# moon-germs.net
KiCad netlist of a schematic drawn in EAGLE
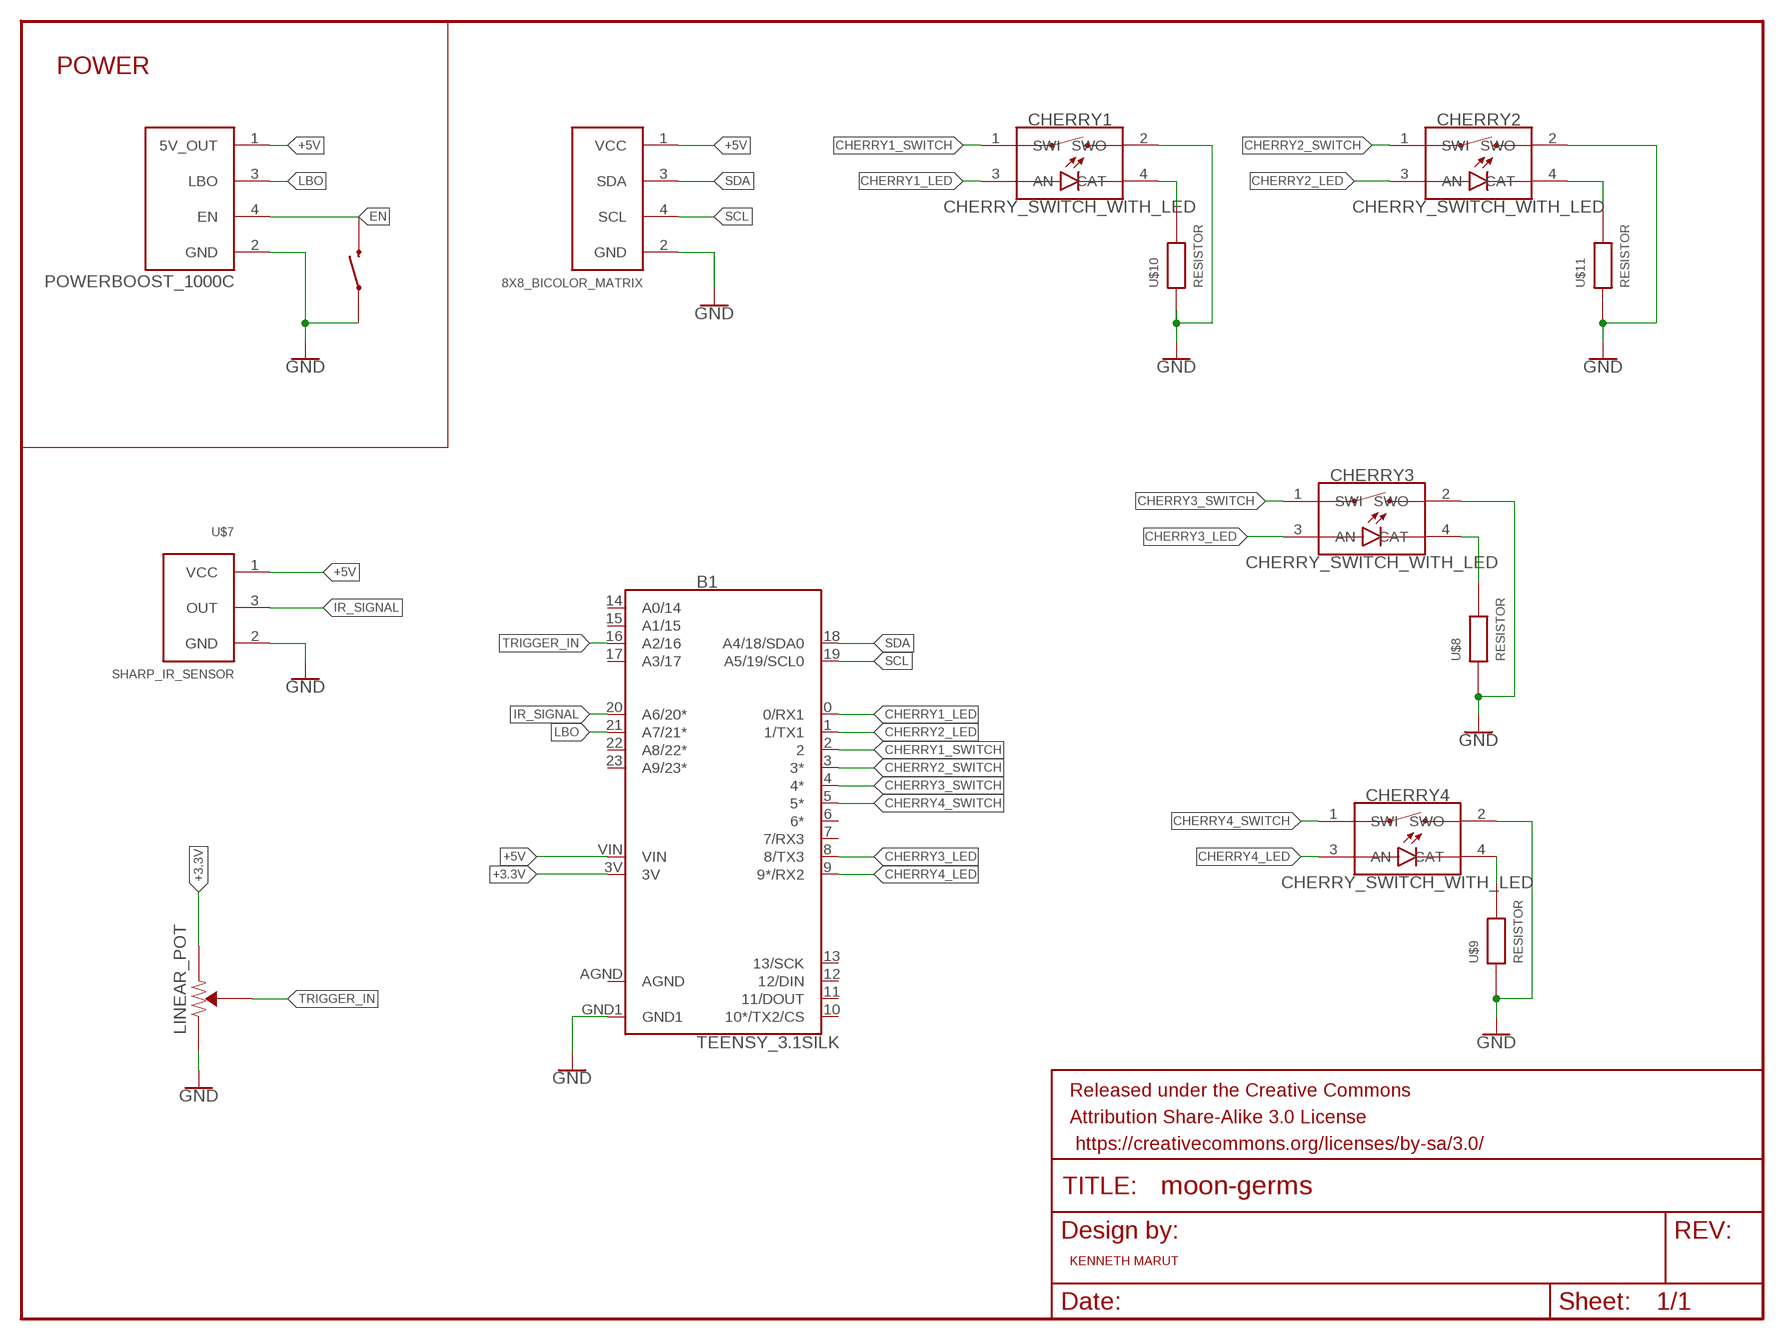
[diagram p0: schematic, sheet 1]

(export (version "E")
  (design (tool "Eeschema 10.0.6"))
  (components
    (comp (ref "B1")
      (value "TEENSY_3.1SILK")
      (footprint "eagle-import:TEENSY_3.1")
      (libsource (lib "eagle-import") (part "TEENSY_3.1SILK"))
    )
    (comp (ref "CHERRY1")
      (value "CHERRY_SWITCH_WITH_LED")
      (footprint "eagle-import:1X04")
      (libsource (lib "eagle-import") (part "CHERRY_SWITCH_WITH_LED"))
    )
    (comp (ref "CHERRY2")
      (value "CHERRY_SWITCH_WITH_LED")
      (footprint "eagle-import:1X04")
      (libsource (lib "eagle-import") (part "CHERRY_SWITCH_WITH_LED"))
    )
    (comp (ref "CHERRY3")
      (value "CHERRY_SWITCH_WITH_LED")
      (footprint "eagle-import:1X04")
      (libsource (lib "eagle-import") (part "CHERRY_SWITCH_WITH_LED"))
    )
    (comp (ref "CHERRY4")
      (value "CHERRY_SWITCH_WITH_LED")
      (footprint "eagle-import:1X04")
      (libsource (lib "eagle-import") (part "CHERRY_SWITCH_WITH_LED"))
    )
    (comp (ref "FRAME1")
      (value "FRAME-LETTER")
      (footprint "eagle-import:CREATIVE_COMMONS")
      (libsource (lib "eagle-import") (part "FRAME-LETTER"))
    )
    (comp (ref "U$1")
      (value "8X8_BICOLOR_MATRIX")
      (footprint "eagle-import:1X04")
      (libsource (lib "eagle-import") (part "8X8_BICOLOR_MATRIX"))
    )
    (comp (ref "U$6")
      (value "SPST-SWITCH")
      (footprint "eagle-import:1X02")
      (libsource (lib "eagle-import") (part "SPST-SWITCH"))
    )
    (comp (ref "U$7")
      (value "SHARP_IR_SENSOR")
      (footprint "eagle-import:1X03")
      (libsource (lib "eagle-import") (part "SHARP_IR_SENSOR"))
    )
    (comp (ref "U$8")
      (value "RESISTOR")
      (footprint "eagle-import:0805")
      (libsource (lib "eagle-import") (part "RESISTOR"))
    )
    (comp (ref "U$9")
      (value "RESISTOR")
      (footprint "eagle-import:0805")
      (libsource (lib "eagle-import") (part "RESISTOR"))
    )
    (comp (ref "U$10")
      (value "RESISTOR")
      (footprint "eagle-import:0805")
      (libsource (lib "eagle-import") (part "RESISTOR"))
    )
    (comp (ref "U$11")
      (value "RESISTOR")
      (footprint "eagle-import:0805")
      (libsource (lib "eagle-import") (part "RESISTOR"))
    )
    (comp (ref "U$12")
      (value "POWERBOOST_1000C")
      (footprint "eagle-import:1X04")
      (libsource (lib "eagle-import") (part "POWERBOOST_1000C"))
    )
    (comp (ref "U$13")
      (value "LINEAR_POT")
      (footprint "eagle-import:1X03")
      (libsource (lib "eagle-import") (part "LINEAR_POT"))
    )
  )
  (nets
    (net (code "1") (name "+3.3V") (class "Default")
      (node (ref "B1") (pin "3V") (pinfunction "3V_3V") (pintype "power_in"))
      (node (ref "U$13") (pin "1") (pinfunction "+_1") (pintype "bidirectional"))
    )
    (net (code "2") (name "+5V") (class "Default")
      (node (ref "B1") (pin "VIN") (pinfunction "VIN_VIN") (pintype "power_in"))
      (node (ref "U$1") (pin "1") (pinfunction "VCC_1") (pintype "bidirectional"))
      (node (ref "U$12") (pin "1") (pinfunction "5V_OUT_1") (pintype "bidirectional"))
      (node (ref "U$7") (pin "1") (pinfunction "VCC_1") (pintype "bidirectional"))
    )
    (net (code "3") (name "/AGND") (class "Default")
      (node (ref "B1") (pin "AGND") (pinfunction "AGND_AGND") (pintype "power_in"))
    )
    (net (code "4") (name "CHERRY1_LED") (class "Default")
      (node (ref "B1") (pin "0") (pinfunction "0/RX1_0") (pintype "bidirectional"))
      (node (ref "CHERRY1") (pin "3") (pinfunction "AN_3") (pintype "bidirectional"))
    )
    (net (code "5") (name "CHERRY1_SWITCH") (class "Default")
      (node (ref "B1") (pin "2") (pinfunction "2_2") (pintype "bidirectional"))
      (node (ref "CHERRY1") (pin "1") (pinfunction "SWI_1") (pintype "bidirectional"))
    )
    (net (code "6") (name "CHERRY2_LED") (class "Default")
      (node (ref "B1") (pin "1") (pinfunction "1/TX1_1") (pintype "bidirectional"))
      (node (ref "CHERRY2") (pin "3") (pinfunction "AN_3") (pintype "bidirectional"))
    )
    (net (code "7") (name "CHERRY2_SWITCH") (class "Default")
      (node (ref "B1") (pin "3") (pinfunction "3*_3") (pintype "bidirectional"))
      (node (ref "CHERRY2") (pin "1") (pinfunction "SWI_1") (pintype "bidirectional"))
    )
    (net (code "8") (name "CHERRY3_LED") (class "Default")
      (node (ref "B1") (pin "8") (pinfunction "8/TX3_8") (pintype "bidirectional"))
      (node (ref "CHERRY3") (pin "3") (pinfunction "AN_3") (pintype "bidirectional"))
    )
    (net (code "9") (name "CHERRY3_SWITCH") (class "Default")
      (node (ref "B1") (pin "4") (pinfunction "4*_4") (pintype "bidirectional"))
      (node (ref "CHERRY3") (pin "1") (pinfunction "SWI_1") (pintype "bidirectional"))
    )
    (net (code "10") (name "CHERRY4_LED") (class "Default")
      (node (ref "B1") (pin "9") (pinfunction "9*/RX2_9") (pintype "bidirectional"))
      (node (ref "CHERRY4") (pin "3") (pinfunction "AN_3") (pintype "bidirectional"))
    )
    (net (code "11") (name "CHERRY4_SWITCH") (class "Default")
      (node (ref "B1") (pin "5") (pinfunction "5*_5") (pintype "bidirectional"))
      (node (ref "CHERRY4") (pin "1") (pinfunction "SWI_1") (pintype "bidirectional"))
    )
    (net (code "12") (name "EN") (class "Default")
      (node (ref "U$12") (pin "4") (pinfunction "EN_4") (pintype "bidirectional"))
      (node (ref "U$6") (pin "2") (pinfunction "SWO_2") (pintype "bidirectional"))
    )
    (net (code "13") (name "GND") (class "Default")
      (node (ref "B1") (pin "GND1") (pinfunction "GND1_GND1") (pintype "power_in"))
      (node (ref "CHERRY1") (pin "2") (pinfunction "SWO_2") (pintype "bidirectional"))
      (node (ref "CHERRY2") (pin "2") (pinfunction "SWO_2") (pintype "bidirectional"))
      (node (ref "CHERRY3") (pin "2") (pinfunction "SWO_2") (pintype "bidirectional"))
      (node (ref "CHERRY4") (pin "2") (pinfunction "SWO_2") (pintype "bidirectional"))
      (node (ref "U$1") (pin "2") (pinfunction "GND_2") (pintype "bidirectional"))
      (node (ref "U$10") (pin "1") (pinfunction "P$1_1") (pintype "bidirectional"))
      (node (ref "U$11") (pin "1") (pinfunction "P$1_1") (pintype "bidirectional"))
      (node (ref "U$12") (pin "2") (pinfunction "GND_2") (pintype "bidirectional"))
      (node (ref "U$13") (pin "3") (pinfunction "-_3") (pintype "bidirectional"))
      (node (ref "U$6") (pin "1") (pinfunction "SWI_1") (pintype "bidirectional"))
      (node (ref "U$7") (pin "2") (pinfunction "GND_2") (pintype "bidirectional"))
      (node (ref "U$8") (pin "1") (pinfunction "P$1_1") (pintype "bidirectional"))
      (node (ref "U$9") (pin "1") (pinfunction "P$1_1") (pintype "bidirectional"))
    )
    (net (code "14") (name "IR_SIGNAL") (class "Default")
      (node (ref "B1") (pin "20") (pinfunction "A6/20*_20") (pintype "bidirectional"))
      (node (ref "U$7") (pin "3") (pinfunction "OUT_3") (pintype "bidirectional"))
    )
    (net (code "15") (name "LBO") (class "Default")
      (node (ref "B1") (pin "21") (pinfunction "A7/21*_21") (pintype "bidirectional"))
      (node (ref "U$12") (pin "3") (pinfunction "LBO_3") (pintype "bidirectional"))
    )
    (net (code "16") (name "Net-(CHERRY1-CAT)") (class "Default")
      (node (ref "CHERRY1") (pin "4") (pinfunction "CAT_4") (pintype "bidirectional"))
      (node (ref "U$10") (pin "2") (pinfunction "P$2_2") (pintype "bidirectional"))
    )
    (net (code "17") (name "Net-(CHERRY2-CAT)") (class "Default")
      (node (ref "CHERRY2") (pin "4") (pinfunction "CAT_4") (pintype "bidirectional"))
      (node (ref "U$11") (pin "2") (pinfunction "P$2_2") (pintype "bidirectional"))
    )
    (net (code "18") (name "Net-(CHERRY3-CAT)") (class "Default")
      (node (ref "CHERRY3") (pin "4") (pinfunction "CAT_4") (pintype "bidirectional"))
      (node (ref "U$8") (pin "2") (pinfunction "P$2_2") (pintype "bidirectional"))
    )
    (net (code "19") (name "Net-(CHERRY4-CAT)") (class "Default")
      (node (ref "CHERRY4") (pin "4") (pinfunction "CAT_4") (pintype "bidirectional"))
      (node (ref "U$9") (pin "2") (pinfunction "P$2_2") (pintype "bidirectional"))
    )
    (net (code "20") (name "SCL") (class "Default")
      (node (ref "B1") (pin "19") (pinfunction "A5/19/SCL0_19") (pintype "bidirectional"))
      (node (ref "U$1") (pin "4") (pinfunction "SCL_4") (pintype "bidirectional"))
    )
    (net (code "21") (name "SDA") (class "Default")
      (node (ref "B1") (pin "18") (pinfunction "A4/18/SDA0_18") (pintype "bidirectional"))
      (node (ref "U$1") (pin "3") (pinfunction "SDA_3") (pintype "bidirectional"))
    )
    (net (code "22") (name "TRIGGER_IN") (class "Default")
      (node (ref "B1") (pin "16") (pinfunction "A2/16_16") (pintype "bidirectional"))
      (node (ref "U$13") (pin "2") (pinfunction "W_2") (pintype "bidirectional"))
    )
    (net (code "23") (name "unconnected-(B1-6*-Pad6)") (class "Default")
      (node (ref "B1") (pin "6") (pinfunction "6*_6") (pintype "bidirectional"))
    )
    (net (code "24") (name "unconnected-(B1-7{slash}RX3-Pad7)") (class "Default")
      (node (ref "B1") (pin "7") (pinfunction "7/RX3_7") (pintype "bidirectional"))
    )
    (net (code "25") (name "unconnected-(B1-10*{slash}TX2{slash}CS-Pad10)") (class "Default")
      (node (ref "B1") (pin "10") (pinfunction "10*/TX2/CS_10") (pintype "bidirectional"))
    )
    (net (code "26") (name "unconnected-(B1-11{slash}DOUT-Pad11)") (class "Default")
      (node (ref "B1") (pin "11") (pinfunction "11/DOUT_11") (pintype "bidirectional"))
    )
    (net (code "27") (name "unconnected-(B1-12{slash}DIN-Pad12)") (class "Default")
      (node (ref "B1") (pin "12") (pinfunction "12/DIN_12") (pintype "bidirectional"))
    )
    (net (code "28") (name "unconnected-(B1-13{slash}SCK-Pad13)") (class "Default")
      (node (ref "B1") (pin "13") (pinfunction "13/SCK_13") (pintype "bidirectional"))
    )
    (net (code "29") (name "unconnected-(B1-A0{slash}14-Pad14)") (class "Default")
      (node (ref "B1") (pin "14") (pinfunction "A0/14_14") (pintype "bidirectional"))
    )
    (net (code "30") (name "unconnected-(B1-A1{slash}15-Pad15)") (class "Default")
      (node (ref "B1") (pin "15") (pinfunction "A1/15_15") (pintype "bidirectional"))
    )
    (net (code "31") (name "unconnected-(B1-A3{slash}17-Pad17)") (class "Default")
      (node (ref "B1") (pin "17") (pinfunction "A3/17_17") (pintype "bidirectional"))
    )
    (net (code "32") (name "unconnected-(B1-A8{slash}22*-Pad22)") (class "Default")
      (node (ref "B1") (pin "22") (pinfunction "A8/22*_22") (pintype "bidirectional"))
    )
    (net (code "33") (name "unconnected-(B1-A9{slash}23*-Pad23)") (class "Default")
      (node (ref "B1") (pin "23") (pinfunction "A9/23*_23") (pintype "bidirectional"))
    )
  )
)
